# MC50_Pwr_MotDrv.net
KiCad netlist of a schematic drawn in Altium Designer
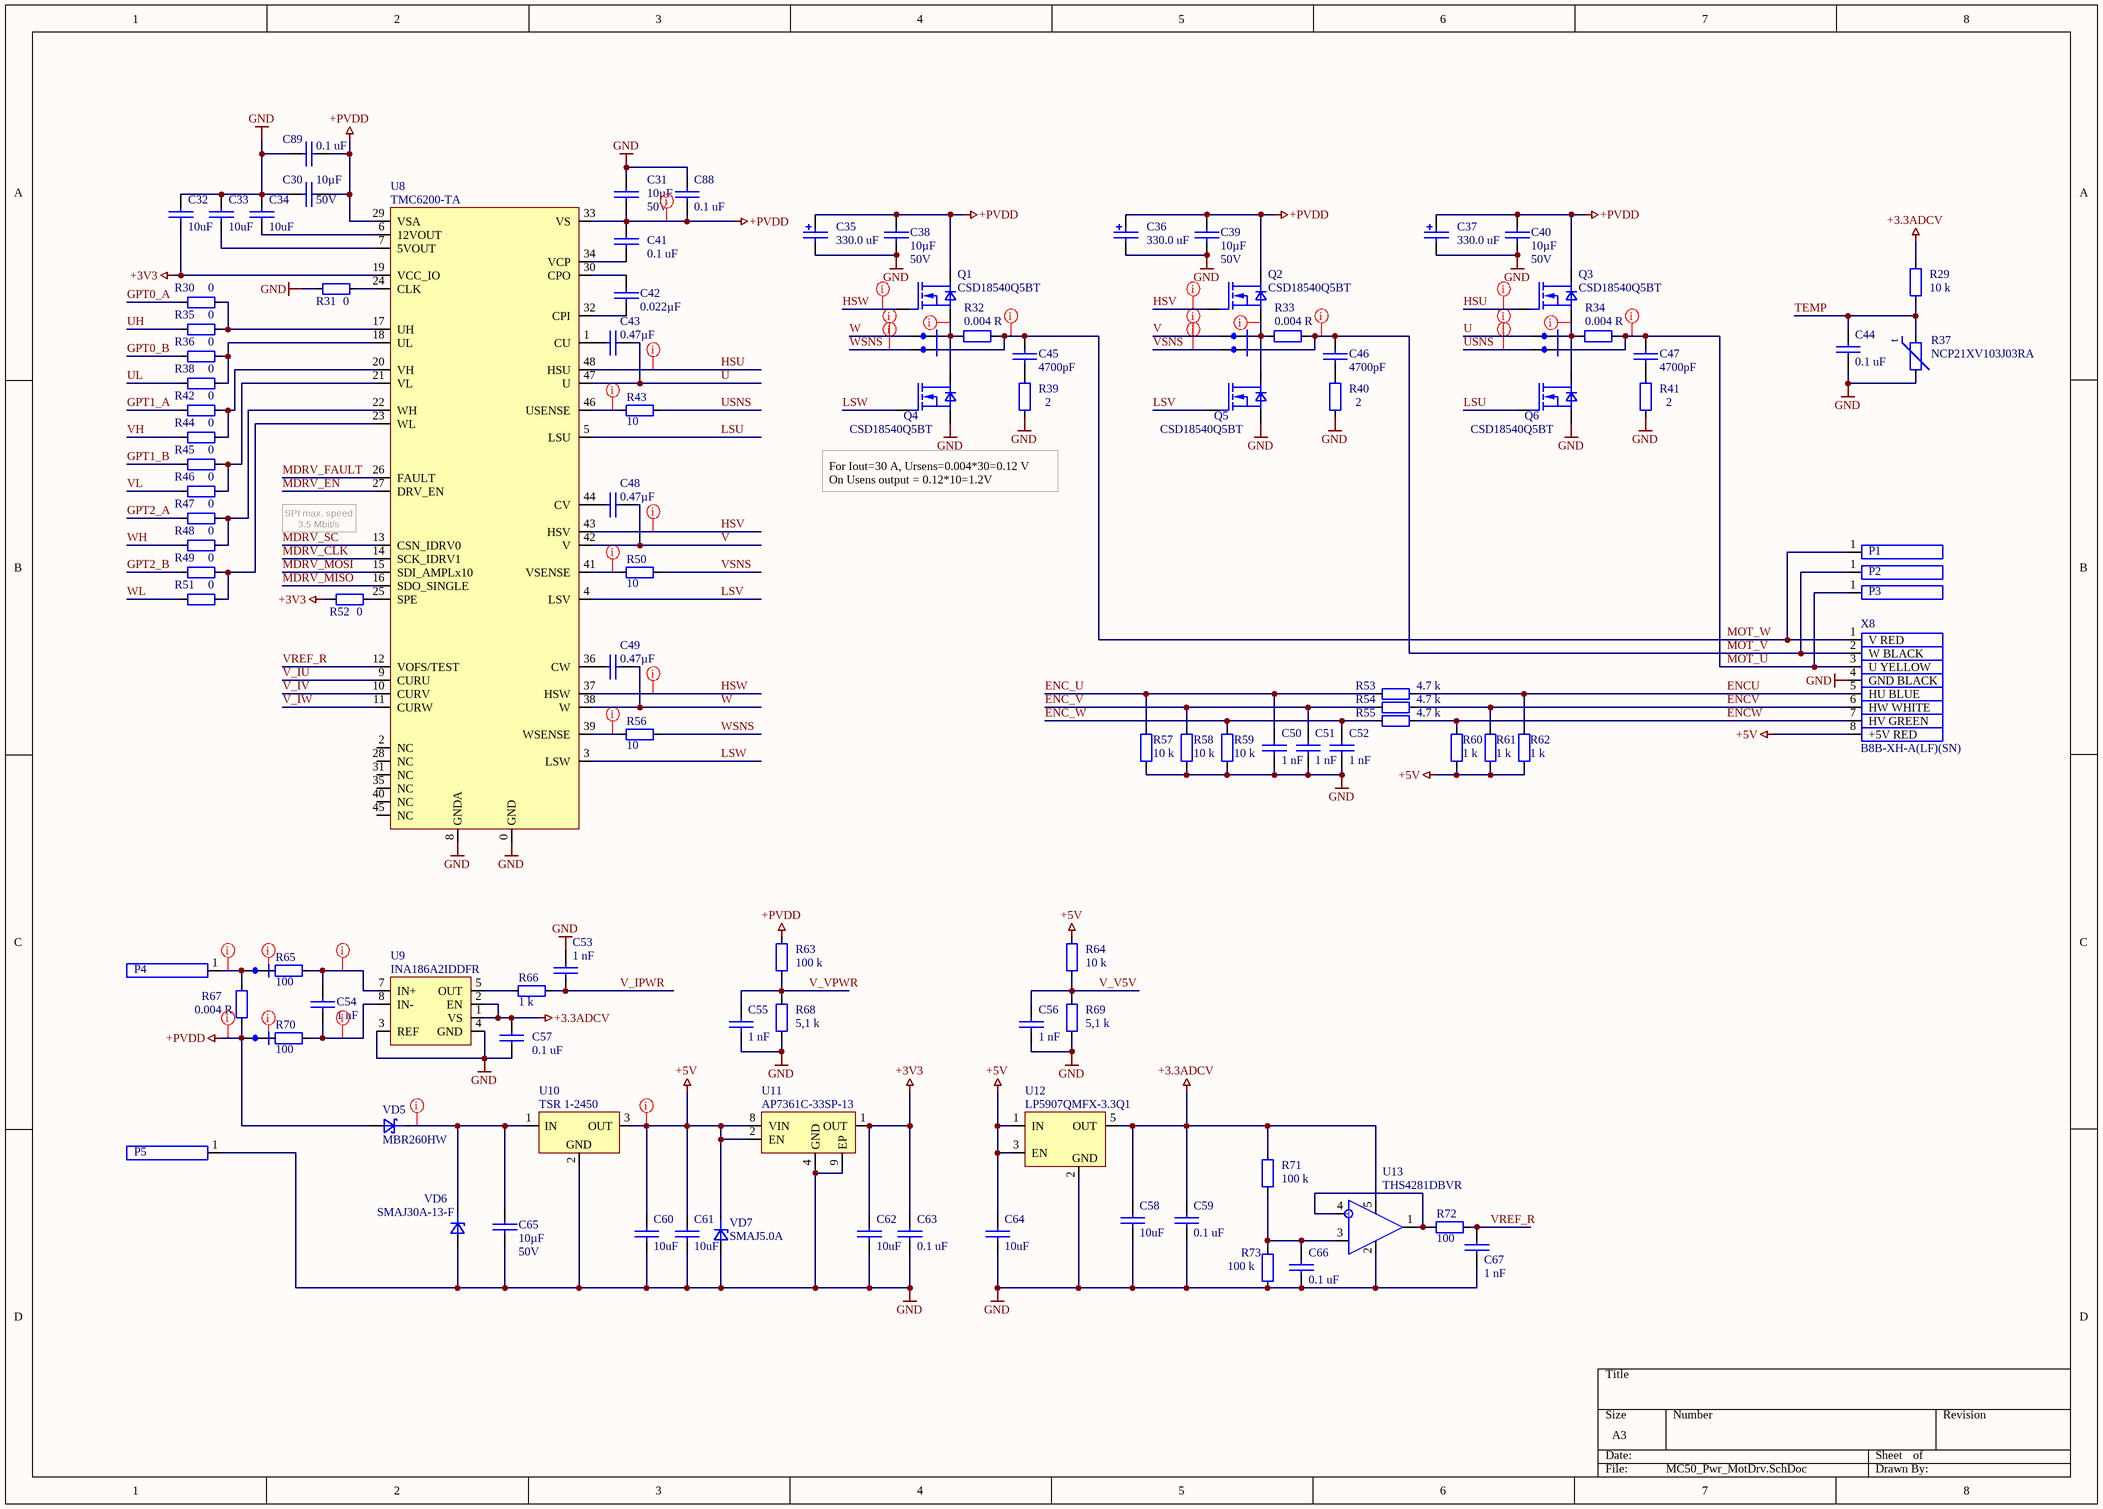
[diagram p0: MC50_Pwr_MotDrv.SchDoc]

(export (version "E")
  (design (tool "Eeschema 10.0.6"))
  (components
    (comp (ref "B1")
      (value "Current shunt net tie 0.4 mm")
      (footprint "Current shunt net tie 0.4 mm")
      (libsource (lib "ea_Net_tie") (part "Current shunt net tie 0.4 mm"))
    )
    (comp (ref "B2")
      (value "Current shunt net tie 0.4 mm")
      (footprint "Current shunt net tie 0.4 mm")
      (libsource (lib "ea_Net_tie") (part "Current shunt net tie 0.4 mm"))
    )
    (comp (ref "B3")
      (value "Current shunt net tie 0.4 mm")
      (footprint "Current shunt net tie 0.4 mm")
      (libsource (lib "ea_Net_tie") (part "Current shunt net tie 0.4 mm"))
    )
    (comp (ref "B4")
      (value "Current shunt net tie 0.4 mm")
      (footprint "Current shunt net tie 0.4 mm")
      (libsource (lib "ea_Net_tie") (part "Current shunt net tie 0.4 mm"))
    )
    (comp (ref "B5")
      (value "Current shunt net tie 0.4 mm")
      (footprint "Current shunt net tie 0.4 mm")
      (libsource (lib "ea_Net_tie") (part "Current shunt net tie 0.4 mm"))
    )
    (comp (ref "B6")
      (value "Current shunt net tie 0.4 mm")
      (footprint "Current shunt net tie 0.4 mm")
      (libsource (lib "ea_Net_tie") (part "Current shunt net tie 0.4 mm"))
    )
    (comp (ref "B7")
      (value "Current shunt net tie 0.4 mm")
      (footprint "Current shunt net tie 0.4 mm")
      (libsource (lib "ea_Net_tie") (part "Current shunt net tie 0.4 mm"))
    )
    (comp (ref "B8")
      (value "Current shunt net tie 0.4 mm")
      (footprint "Current shunt net tie 0.4 mm")
      (libsource (lib "ea_Net_tie") (part "Current shunt net tie 0.4 mm"))
    )
    (comp (ref "C30")
      (value "10µF")
      (footprint "1210 CAP")
      (description "10µF, ±10%, 50V, X7S, 1210 (3225 Metric), -55°C ~ 125°C, -, Automotive")
      (fields
        (field (name "VOLTAGE - RATED") "50V")
        (field (name "PART NUMBER") "GCM32EC71H106KA03K")
        (field (name "MANUFACTURER") "Murata Electronics North America")
      )
      (libsource (lib "ea_PassivComps") (part "Capacitor"))
    )
    (comp (ref "C31")
      (value "10µF")
      (footprint "1210 CAP")
      (description "10µF, ±10%, 50V, X7S, 1210 (3225 Metric), -55°C ~ 125°C, -, Automotive")
      (fields
        (field (name "VOLTAGE - RATED") "50V")
        (field (name "PART NUMBER") "GCM32EC71H106KA03K")
        (field (name "MANUFACTURER") "Murata Electronics North America")
      )
      (libsource (lib "ea_PassivComps") (part "Capacitor"))
    )
    (comp (ref "C32")
      (value "10uF")
      (footprint "1608[0603]")
      (description "10 µF ±10% 25V Ceramic Capacitor X5R 0603 (1608 Metric), -55°C ~ 85°C")
      (fields (field (name "MANUFACTURER") "Murata Electronics") (field (name "TOLERANCE") "±10%"))
      (libsource (lib "ea_Capacitors_0603") (part "GRM188R61E106KA73D"))
    )
    (comp (ref "C33")
      (value "10uF")
      (footprint "1608[0603]")
      (description "10 µF ±10% 25V Ceramic Capacitor X5R 0603 (1608 Metric), -55°C ~ 85°C")
      (fields (field (name "MANUFACTURER") "Murata Electronics") (field (name "TOLERANCE") "±10%"))
      (libsource (lib "ea_Capacitors_0603") (part "GRM188R61E106KA73D"))
    )
    (comp (ref "C34")
      (value "10uF")
      (footprint "1608[0603]")
      (description "10 µF ±10% 25V Ceramic Capacitor X5R 0603 (1608 Metric), -55°C ~ 85°C")
      (fields (field (name "MANUFACTURER") "Murata Electronics") (field (name "TOLERANCE") "±10%"))
      (libsource (lib "ea_Capacitors_0603") (part "GRM188R61E106KA73D"))
    )
    (comp (ref "C35")
      (value "330.0 uF")
      (footprint "UUD1V331MNL1GS")
      (description "330 uF, 50V, 120 mOhm @ 100kHz, 585 mA, 10x10, -50...+105 C")
      (fields (field (name "MANUFACTURER") "Panasonic Electronic Components") (field (name "VOLTAGE") "50 V"))
      (libsource (lib "ea_Capacitors") (part "EEE-FT1H331AP"))
    )
    (comp (ref "C36")
      (value "330.0 uF")
      (footprint "UUD1V331MNL1GS")
      (description "330 uF, 50V, 120 mOhm @ 100kHz, 585 mA, 10x10, -50...+105 C")
      (fields (field (name "MANUFACTURER") "Panasonic Electronic Components") (field (name "VOLTAGE") "50 V"))
      (libsource (lib "ea_Capacitors") (part "EEE-FT1H331AP"))
    )
    (comp (ref "C37")
      (value "330.0 uF")
      (footprint "UUD1V331MNL1GS")
      (description "330 uF, 50V, 120 mOhm @ 100kHz, 585 mA, 10x10, -50...+105 C")
      (fields (field (name "MANUFACTURER") "Panasonic Electronic Components") (field (name "VOLTAGE") "50 V"))
      (libsource (lib "ea_Capacitors") (part "EEE-FT1H331AP"))
    )
    (comp (ref "C38")
      (value "10µF")
      (footprint "1210 CAP")
      (description "10µF, ±10%, 50V, X7S, 1210 (3225 Metric), -55°C ~ 125°C, -, Automotive")
      (fields
        (field (name "VOLTAGE - RATED") "50V")
        (field (name "PART NUMBER") "GCM32EC71H106KA03K")
        (field (name "MANUFACTURER") "Murata Electronics North America")
      )
      (libsource (lib "ea_PassivComps") (part "Capacitor"))
    )
    (comp (ref "C39")
      (value "10µF")
      (footprint "1210 CAP")
      (description "10µF, ±10%, 50V, X7S, 1210 (3225 Metric), -55°C ~ 125°C, -, Automotive")
      (fields
        (field (name "VOLTAGE - RATED") "50V")
        (field (name "PART NUMBER") "GCM32EC71H106KA03K")
        (field (name "MANUFACTURER") "Murata Electronics North America")
      )
      (libsource (lib "ea_PassivComps") (part "Capacitor"))
    )
    (comp (ref "C40")
      (value "10µF")
      (footprint "1210 CAP")
      (description "10µF, ±10%, 50V, X7S, 1210 (3225 Metric), -55°C ~ 125°C, -, Automotive")
      (fields
        (field (name "VOLTAGE - RATED") "50V")
        (field (name "PART NUMBER") "GCM32EC71H106KA03K")
        (field (name "MANUFACTURER") "Murata Electronics North America")
      )
      (libsource (lib "ea_PassivComps") (part "Capacitor"))
    )
    (comp (ref "C41")
      (value "0.1 uF")
      (footprint "1608[0603]")
      (description "0.1 µF ±10% 50V Ceramic Capacitor X7R 0603 (1608 Metric),  \r\n-55°C ~ 125°C")
      (fields
        (field (name "TOLERANCE") "+-10%")
        (field (name "MANUFACTURER") "Walsin Technology Corporation")
      )
      (libsource (lib "ea_Capacitors_0603") (part "0603B104K500CT"))
    )
    (comp (ref "C42")
      (value "0.022µF")
      (footprint "0603 CAP")
      (description "0.022µF, ±10%, 50V, X7R, 0603 (1608 Metric), -55°C ~ 125°C, -, General Purpose")
      (fields (field (name "PART NUMBER") "06035C223KAT4A") (field (name "MANUFACTURER") "AVX Corporation"))
      (libsource (lib "ea_PassivComps") (part "Capacitor"))
    )
    (comp (ref "C43")
      (value "0.47µF")
      (footprint "0603 CAP")
      (description "0.47µF, -20%, +80%, 50V, Y5V (F), 0603 (1608 Metric), -30°C ~ 85°C, -, General Purpose")
      (fields
        (field (name "PART NUMBER") "CL10F474ZB8NNNC")
        (field (name "MANUFACTURER") "Samsung Electro-Mechanics")
      )
      (libsource (lib "ea_PassivComps") (part "Capacitor"))
    )
    (comp (ref "C44")
      (value "0.1 uF")
      (footprint "1608[0603]")
      (description "0.1 µF ±10% 50V Ceramic Capacitor X7R 0603 (1608 Metric),  \r\n-55°C ~ 125°C")
      (fields
        (field (name "TOLERANCE") "+-10%")
        (field (name "MANUFACTURER") "Walsin Technology Corporation")
      )
      (libsource (lib "ea_Capacitors_0603") (part "0603B104K500CT"))
    )
    (comp (ref "C45")
      (value "4700pF")
      (footprint "0805 CAP")
      (description "4700pF, ±10%, 100V, X7R, 0805 (2012 Metric), -55°C ~ 125°C, -, General Purpose")
      (fields
        (field (name "PART NUMBER") "CL21B472KCANNNC")
        (field (name "MANUFACTURER") "Samsung Electro-Mechanics")
      )
      (libsource (lib "ea_PassivComps") (part "Capacitor"))
    )
    (comp (ref "C46")
      (value "4700pF")
      (footprint "0805 CAP")
      (description "4700pF, ±10%, 100V, X7R, 0805 (2012 Metric), -55°C ~ 125°C, -, General Purpose")
      (fields
        (field (name "PART NUMBER") "CL21B472KCANNNC")
        (field (name "MANUFACTURER") "Samsung Electro-Mechanics")
      )
      (libsource (lib "ea_PassivComps") (part "Capacitor"))
    )
    (comp (ref "C47")
      (value "4700pF")
      (footprint "0805 CAP")
      (description "4700pF, ±10%, 100V, X7R, 0805 (2012 Metric), -55°C ~ 125°C, -, General Purpose")
      (fields
        (field (name "PART NUMBER") "CL21B472KCANNNC")
        (field (name "MANUFACTURER") "Samsung Electro-Mechanics")
      )
      (libsource (lib "ea_PassivComps") (part "Capacitor"))
    )
    (comp (ref "C48")
      (value "0.47µF")
      (footprint "0603 CAP")
      (description "0.47µF, -20%, +80%, 50V, Y5V (F), 0603 (1608 Metric), -30°C ~ 85°C, -, General Purpose")
      (fields
        (field (name "PART NUMBER") "CL10F474ZB8NNNC")
        (field (name "MANUFACTURER") "Samsung Electro-Mechanics")
      )
      (libsource (lib "ea_PassivComps") (part "Capacitor"))
    )
    (comp (ref "C49")
      (value "0.47µF")
      (footprint "0603 CAP")
      (description "0.47µF, -20%, +80%, 50V, Y5V (F), 0603 (1608 Metric), -30°C ~ 85°C, -, General Purpose")
      (fields
        (field (name "PART NUMBER") "CL10F474ZB8NNNC")
        (field (name "MANUFACTURER") "Samsung Electro-Mechanics")
      )
      (libsource (lib "ea_PassivComps") (part "Capacitor"))
    )
    (comp (ref "C50")
      (value "1 nF")
      (footprint "0603 CAP")
      (description "1000pF, ±5%, 50V, X7R, 0603 (1608 Metric), -55°C ~ 125°C, -, General Purpose")
      (fields (field (name "PART NUMBER") "CC0603JRX7R9BB102") (field (name "MANUFACTURER") "Yageo"))
      (libsource (lib "ea_PassivComps") (part "Capacitor"))
    )
    (comp (ref "C51")
      (value "1 nF")
      (footprint "0603 CAP")
      (description "1000pF, ±5%, 50V, X7R, 0603 (1608 Metric), -55°C ~ 125°C, -, General Purpose")
      (fields (field (name "PART NUMBER") "CC0603JRX7R9BB102") (field (name "MANUFACTURER") "Yageo"))
      (libsource (lib "ea_PassivComps") (part "Capacitor"))
    )
    (comp (ref "C52")
      (value "1 nF")
      (footprint "0603 CAP")
      (description "1000pF, ±5%, 50V, X7R, 0603 (1608 Metric), -55°C ~ 125°C, -, General Purpose")
      (fields (field (name "PART NUMBER") "CC0603JRX7R9BB102") (field (name "MANUFACTURER") "Yageo"))
      (libsource (lib "ea_PassivComps") (part "Capacitor"))
    )
    (comp (ref "C53")
      (value "1 nF")
      (footprint "0603 CAP")
      (description "1000pF, ±5%, 50V, X7R, 0603 (1608 Metric), -55°C ~ 125°C, -, General Purpose")
      (fields (field (name "PART NUMBER") "CC0603JRX7R9BB102") (field (name "MANUFACTURER") "Yageo"))
      (libsource (lib "ea_PassivComps") (part "Capacitor"))
    )
    (comp (ref "C54")
      (value "1 nF")
      (footprint "0603 CAP")
      (description "1000pF, ±5%, 50V, X7R, 0603 (1608 Metric), -55°C ~ 125°C, -, General Purpose")
      (fields (field (name "PART NUMBER") "CC0603JRX7R9BB102") (field (name "MANUFACTURER") "Yageo"))
      (libsource (lib "ea_PassivComps") (part "Capacitor"))
    )
    (comp (ref "C55")
      (value "1 nF")
      (footprint "0603 CAP")
      (description "1000pF, ±5%, 50V, X7R, 0603 (1608 Metric), -55°C ~ 125°C, -, General Purpose")
      (fields (field (name "PART NUMBER") "CC0603JRX7R9BB102") (field (name "MANUFACTURER") "Yageo"))
      (libsource (lib "ea_PassivComps") (part "Capacitor"))
    )
    (comp (ref "C56")
      (value "1 nF")
      (footprint "0603 CAP")
      (description "1000pF, ±5%, 50V, X7R, 0603 (1608 Metric), -55°C ~ 125°C, -, General Purpose")
      (fields (field (name "PART NUMBER") "CC0603JRX7R9BB102") (field (name "MANUFACTURER") "Yageo"))
      (libsource (lib "ea_PassivComps") (part "Capacitor"))
    )
    (comp (ref "C57")
      (value "0.1 uF")
      (footprint "1608[0603]")
      (description "0.1 µF ±10% 50V Ceramic Capacitor X7R 0603 (1608 Metric),  \r\n-55°C ~ 125°C")
      (fields
        (field (name "TOLERANCE") "+-10%")
        (field (name "MANUFACTURER") "Walsin Technology Corporation")
      )
      (libsource (lib "ea_Capacitors_0603") (part "0603B104K500CT"))
    )
    (comp (ref "C58")
      (value "10uF")
      (footprint "1608[0603]")
      (description "10 µF ±10% 25V Ceramic Capacitor X5R 0603 (1608 Metric), -55°C ~ 85°C")
      (fields (field (name "MANUFACTURER") "Murata Electronics") (field (name "TOLERANCE") "±10%"))
      (libsource (lib "ea_Capacitors_0603") (part "GRM188R61E106KA73D"))
    )
    (comp (ref "C59")
      (value "0.1 uF")
      (footprint "1608[0603]")
      (description "0.1 µF ±10% 50V Ceramic Capacitor X7R 0603 (1608 Metric),  \r\n-55°C ~ 125°C")
      (fields
        (field (name "TOLERANCE") "+-10%")
        (field (name "MANUFACTURER") "Walsin Technology Corporation")
      )
      (libsource (lib "ea_Capacitors_0603") (part "0603B104K500CT"))
    )
    (comp (ref "C60")
      (value "10uF")
      (footprint "1608[0603]")
      (description "10 µF ±10% 25V Ceramic Capacitor X5R 0603 (1608 Metric), -55°C ~ 85°C")
      (fields (field (name "MANUFACTURER") "Murata Electronics") (field (name "TOLERANCE") "±10%"))
      (libsource (lib "ea_Capacitors_0603") (part "GRM188R61E106KA73D"))
    )
    (comp (ref "C61")
      (value "10uF")
      (footprint "1608[0603]")
      (description "10 µF ±10% 25V Ceramic Capacitor X5R 0603 (1608 Metric), -55°C ~ 85°C")
      (fields (field (name "MANUFACTURER") "Murata Electronics") (field (name "TOLERANCE") "±10%"))
      (libsource (lib "ea_Capacitors_0603") (part "GRM188R61E106KA73D"))
    )
    (comp (ref "C62")
      (value "10uF")
      (footprint "1608[0603]")
      (description "10 µF ±10% 25V Ceramic Capacitor X5R 0603 (1608 Metric), -55°C ~ 85°C")
      (fields (field (name "MANUFACTURER") "Murata Electronics") (field (name "TOLERANCE") "±10%"))
      (libsource (lib "ea_Capacitors_0603") (part "GRM188R61E106KA73D"))
    )
    (comp (ref "C63")
      (value "0.1 uF")
      (footprint "1608[0603]")
      (description "0.1 µF ±10% 50V Ceramic Capacitor X7R 0603 (1608 Metric),  \r\n-55°C ~ 125°C")
      (fields
        (field (name "TOLERANCE") "+-10%")
        (field (name "MANUFACTURER") "Walsin Technology Corporation")
      )
      (libsource (lib "ea_Capacitors_0603") (part "0603B104K500CT"))
    )
    (comp (ref "C64")
      (value "10uF")
      (footprint "1608[0603]")
      (description "10 µF ±10% 25V Ceramic Capacitor X5R 0603 (1608 Metric), -55°C ~ 85°C")
      (fields (field (name "MANUFACTURER") "Murata Electronics") (field (name "TOLERANCE") "±10%"))
      (libsource (lib "ea_Capacitors_0603") (part "GRM188R61E106KA73D"))
    )
    (comp (ref "C65")
      (value "10µF")
      (footprint "1210 CAP")
      (description "10µF, ±10%, 50V, X7S, 1210 (3225 Metric), -55°C ~ 125°C, -, Automotive")
      (fields
        (field (name "VOLTAGE - RATED") "50V")
        (field (name "PART NUMBER") "GCM32EC71H106KA03K")
        (field (name "MANUFACTURER") "Murata Electronics North America")
      )
      (libsource (lib "ea_PassivComps") (part "Capacitor"))
    )
    (comp (ref "C66")
      (value "0.1 uF")
      (footprint "1608[0603]")
      (description "0.1 µF ±10% 50V Ceramic Capacitor X7R 0603 (1608 Metric),  \r\n-55°C ~ 125°C")
      (fields
        (field (name "TOLERANCE") "+-10%")
        (field (name "MANUFACTURER") "Walsin Technology Corporation")
      )
      (libsource (lib "ea_Capacitors_0603") (part "0603B104K500CT"))
    )
    (comp (ref "C67")
      (value "1 nF")
      (footprint "0603 CAP")
      (description "1000pF, ±5%, 50V, X7R, 0603 (1608 Metric), -55°C ~ 125°C, -, General Purpose")
      (fields (field (name "PART NUMBER") "CC0603JRX7R9BB102") (field (name "MANUFACTURER") "Yageo"))
      (libsource (lib "ea_PassivComps") (part "Capacitor"))
    )
    (comp (ref "C88")
      (value "0.1 uF")
      (footprint "1608[0603]")
      (description "0.1 µF ±10% 50V Ceramic Capacitor X7R 0603 (1608 Metric),  \r\n-55°C ~ 125°C")
      (fields
        (field (name "TOLERANCE") "+-10%")
        (field (name "MANUFACTURER") "Walsin Technology Corporation")
      )
      (libsource (lib "ea_Capacitors_0603") (part "0603B104K500CT"))
    )
    (comp (ref "C89")
      (value "0.1 uF")
      (footprint "1608[0603]")
      (description "0.1 µF ±10% 50V Ceramic Capacitor X7R 0603 (1608 Metric),  \r\n-55°C ~ 125°C")
      (fields
        (field (name "TOLERANCE") "+-10%")
        (field (name "MANUFACTURER") "Walsin Technology Corporation")
      )
      (libsource (lib "ea_Capacitors_0603") (part "0603B104K500CT"))
    )
    (comp (ref "P1")
      (value "Keystone 1212")
      (footprint "Keystone 1212")
      (description "(4.75mm) Quick Connect Male Solder Connector Non-Insulated")
      (fields (field (name "MANUFACTURER") "Keystone Electronics") (field (name "PARTNUM") "36-1212-ND"))
      (libsource (lib "ea_Connectors_Power") (part "Keystone_1212"))
    )
    (comp (ref "P2")
      (value "Keystone 1212")
      (footprint "Keystone 1212")
      (description "(4.75mm) Quick Connect Male Solder Connector Non-Insulated")
      (fields (field (name "MANUFACTURER") "Keystone Electronics") (field (name "PARTNUM") "36-1212-ND"))
      (libsource (lib "ea_Connectors_Power") (part "Keystone_1212"))
    )
    (comp (ref "P3")
      (value "Keystone 1212")
      (footprint "Keystone 1212")
      (description "(4.75mm) Quick Connect Male Solder Connector Non-Insulated")
      (fields (field (name "MANUFACTURER") "Keystone Electronics") (field (name "PARTNUM") "36-1212-ND"))
      (libsource (lib "ea_Connectors_Power") (part "Keystone_1212"))
    )
    (comp (ref "P4")
      (value "Keystone 1212")
      (footprint "Keystone 1212")
      (description "(4.75mm) Quick Connect Male Solder Connector Non-Insulated")
      (fields (field (name "MANUFACTURER") "Keystone Electronics") (field (name "PARTNUM") "36-1212-ND"))
      (libsource (lib "ea_Connectors_Power") (part "Keystone_1212"))
    )
    (comp (ref "P5")
      (value "Keystone 1212")
      (footprint "Keystone 1212")
      (description "(4.75mm) Quick Connect Male Solder Connector Non-Insulated")
      (fields (field (name "MANUFACTURER") "Keystone Electronics") (field (name "PARTNUM") "36-1212-ND"))
      (libsource (lib "ea_Connectors_Power") (part "Keystone_1212"))
    )
    (comp (ref "Q1")
      (value "CSD18540Q5BT")
      (footprint "SO8FL Universal Footprint")
      (description "MOSFET N-CH, 100 A, 60V, Vgs=±20V, 1.8 mOhm, 41nC @ 10V, 5-DFN (5x6), -55°C ~ 150°C")
      (fields (field (name "MANUFACTURER") "Texas Instruments") (field (name "PARTNUM") "296-37963-1-ND"))
      (libsource (lib "ea_MOSFET_&_drivers") (part "CSD18540Q5BT"))
    )
    (comp (ref "Q2")
      (value "CSD18540Q5BT")
      (footprint "SO8FL Universal Footprint")
      (description "MOSFET N-CH, 100 A, 60V, Vgs=±20V, 1.8 mOhm, 41nC @ 10V, 5-DFN (5x6), -55°C ~ 150°C")
      (fields (field (name "MANUFACTURER") "Texas Instruments") (field (name "PARTNUM") "296-37963-1-ND"))
      (libsource (lib "ea_MOSFET_&_drivers") (part "CSD18540Q5BT"))
    )
    (comp (ref "Q3")
      (value "CSD18540Q5BT")
      (footprint "SO8FL Universal Footprint")
      (description "MOSFET N-CH, 100 A, 60V, Vgs=±20V, 1.8 mOhm, 41nC @ 10V, 5-DFN (5x6), -55°C ~ 150°C")
      (fields (field (name "MANUFACTURER") "Texas Instruments") (field (name "PARTNUM") "296-37963-1-ND"))
      (libsource (lib "ea_MOSFET_&_drivers") (part "CSD18540Q5BT"))
    )
    (comp (ref "Q4")
      (value "CSD18540Q5BT")
      (footprint "SO8FL Universal Footprint")
      (description "MOSFET N-CH, 100 A, 60V, Vgs=±20V, 1.8 mOhm, 41nC @ 10V, 5-DFN (5x6), -55°C ~ 150°C")
      (fields (field (name "MANUFACTURER") "Texas Instruments") (field (name "PARTNUM") "296-37963-1-ND"))
      (libsource (lib "ea_MOSFET_&_drivers") (part "CSD18540Q5BT"))
    )
    (comp (ref "Q5")
      (value "CSD18540Q5BT")
      (footprint "SO8FL Universal Footprint")
      (description "MOSFET N-CH, 100 A, 60V, Vgs=±20V, 1.8 mOhm, 41nC @ 10V, 5-DFN (5x6), -55°C ~ 150°C")
      (fields (field (name "MANUFACTURER") "Texas Instruments") (field (name "PARTNUM") "296-37963-1-ND"))
      (libsource (lib "ea_MOSFET_&_drivers") (part "CSD18540Q5BT"))
    )
    (comp (ref "Q6")
      (value "CSD18540Q5BT")
      (footprint "SO8FL Universal Footprint")
      (description "MOSFET N-CH, 100 A, 60V, Vgs=±20V, 1.8 mOhm, 41nC @ 10V, 5-DFN (5x6), -55°C ~ 150°C")
      (fields (field (name "MANUFACTURER") "Texas Instruments") (field (name "PARTNUM") "296-37963-1-ND"))
      (libsource (lib "ea_MOSFET_&_drivers") (part "CSD18540Q5BT"))
    )
    (comp (ref "R29")
      (value "10 k")
      (footprint "0603")
      (fields
        (field (name "MANUFACTURER") "Stackpole Electronics Inc")
        (field (name "TOLERANCE") "±0.1%")
        (field (name "VOLTAGE") "75V")
      )
      (libsource (lib "ea_PassivComps") (part "Resistor"))
    )
    (comp (ref "R30")
      (value "0")
      (footprint "0603")
      (description "0 Ohms, 0.1W, 1/10W, Thick Film, 0603 (1608 Metric), -55°C ~ 155°C, Automotive AEC-Q200")
      (fields
        (field (name "MANUFACTURER") "Stackpole Electronics Inc.")
        (field (name "PARTNUM") "RMCF0603ZT0R00CT-ND")
      )
      (libsource (lib "") (part "Resistor_1"))
    )
    (comp (ref "R31")
      (value "0")
      (footprint "0603")
      (description "0 Ohms, 0.1W, 1/10W, Thick Film, 0603 (1608 Metric), -55°C ~ 155°C, Automotive AEC-Q200")
      (fields
        (field (name "MANUFACTURER") "Stackpole Electronics Inc.")
        (field (name "PARTNUM") "RMCF0603ZT0R00CT-ND")
      )
      (libsource (lib "") (part "Resistor_1"))
    )
    (comp (ref "R32")
      (value "0.004 R")
      (footprint "CSNL2512 CURR SENS")
      (description "Curr.sens.res. 0.004 OHM, 2W, 1% , ±50ppm/°C, 2512 (6432 Metric)")
      (fields (field (name "MANUFACTURER") "Stackpole Electronics Inc.") (field (name "TOLERANCE") "±1%"))
      (libsource (lib "ea_Resistors") (part "CSNL2512FT4L00"))
    )
    (comp (ref "R33")
      (value "0.004 R")
      (footprint "CSNL2512 CURR SENS")
      (description "Curr.sens.res. 0.004 OHM, 2W, 1% , ±50ppm/°C, 2512 (6432 Metric)")
      (fields (field (name "MANUFACTURER") "Stackpole Electronics Inc.") (field (name "TOLERANCE") "±1%"))
      (libsource (lib "ea_Resistors") (part "CSNL2512FT4L00"))
    )
    (comp (ref "R34")
      (value "0.004 R")
      (footprint "CSNL2512 CURR SENS")
      (description "Curr.sens.res. 0.004 OHM, 2W, 1% , ±50ppm/°C, 2512 (6432 Metric)")
      (fields (field (name "MANUFACTURER") "Stackpole Electronics Inc.") (field (name "TOLERANCE") "±1%"))
      (libsource (lib "ea_Resistors") (part "CSNL2512FT4L00"))
    )
    (comp (ref "R35")
      (value "0")
      (footprint "0603")
      (description "0 Ohms, 0.1W, 1/10W, Thick Film, 0603 (1608 Metric), -55°C ~ 155°C, Automotive AEC-Q200")
      (fields
        (field (name "MANUFACTURER") "Stackpole Electronics Inc.")
        (field (name "PARTNUM") "RMCF0603ZT0R00CT-ND")
      )
      (libsource (lib "") (part "Resistor_1"))
    )
    (comp (ref "R36")
      (value "0")
      (footprint "0603")
      (description "0 Ohms, 0.1W, 1/10W, Thick Film, 0603 (1608 Metric), -55°C ~ 155°C, Automotive AEC-Q200")
      (fields
        (field (name "MANUFACTURER") "Stackpole Electronics Inc.")
        (field (name "PARTNUM") "RMCF0603ZT0R00CT-ND")
      )
      (libsource (lib "") (part "Resistor_1"))
    )
    (comp (ref "R37")
      (value "NCP21XV103J03RA")
      (footprint "0805")
      (description "Thermistor 10k, 0805, NTC")
      (fields (field (name "MANUFACTURER") "Murata") (field (name "PARTNUM") "490-2456-1-ND"))
      (libsource (lib "ea_IC_sensors") (part "NCP21XV103J03RA"))
    )
    (comp (ref "R38")
      (value "0")
      (footprint "0603")
      (description "0 Ohms, 0.1W, 1/10W, Thick Film, 0603 (1608 Metric), -55°C ~ 155°C, Automotive AEC-Q200")
      (fields
        (field (name "MANUFACTURER") "Stackpole Electronics Inc.")
        (field (name "PARTNUM") "RMCF0603ZT0R00CT-ND")
      )
      (libsource (lib "") (part "Resistor_1"))
    )
    (comp (ref "R39")
      (value "2")
      (footprint "0805")
      (description "2 Ohms, ±1%, 0.125W, 1/8W, Thick Film, ±100ppm/°C, 0805 (2012 Metric), -55°C ~ 155°C, -")
      (fields (field (name "MANUFACTURER") "Vishay Dale") (field (name "TOLERANCE") "±1%"))
      (libsource (lib "ea_PassivComps") (part "Resistor"))
    )
    (comp (ref "R40")
      (value "2")
      (footprint "0805")
      (description "2 Ohms, ±1%, 0.125W, 1/8W, Thick Film, ±100ppm/°C, 0805 (2012 Metric), -55°C ~ 155°C, -")
      (fields (field (name "MANUFACTURER") "Vishay Dale") (field (name "TOLERANCE") "±1%"))
      (libsource (lib "ea_PassivComps") (part "Resistor"))
    )
    (comp (ref "R41")
      (value "2")
      (footprint "0805")
      (description "2 Ohms, ±1%, 0.125W, 1/8W, Thick Film, ±100ppm/°C, 0805 (2012 Metric), -55°C ~ 155°C, -")
      (fields (field (name "MANUFACTURER") "Vishay Dale") (field (name "TOLERANCE") "±1%"))
      (libsource (lib "ea_PassivComps") (part "Resistor"))
    )
    (comp (ref "R42")
      (value "0")
      (footprint "0603")
      (description "0 Ohms, 0.1W, 1/10W, Thick Film, 0603 (1608 Metric), -55°C ~ 155°C, Automotive AEC-Q200")
      (fields
        (field (name "MANUFACTURER") "Stackpole Electronics Inc.")
        (field (name "PARTNUM") "RMCF0603ZT0R00CT-ND")
      )
      (libsource (lib "") (part "Resistor_1"))
    )
    (comp (ref "R43")
      (value "10")
      (footprint "0603")
      (fields
        (field (name "MANUFACTURER") "Panasonic Electronic Components")
        (field (name "TOLERANCE") "±1%")
        (field (name "VOLTAGE") "75V")
      )
      (libsource (lib "") (part "Resistor_1"))
    )
    (comp (ref "R44")
      (value "0")
      (footprint "0603")
      (description "0 Ohms, 0.1W, 1/10W, Thick Film, 0603 (1608 Metric), -55°C ~ 155°C, Automotive AEC-Q200")
      (fields
        (field (name "MANUFACTURER") "Stackpole Electronics Inc.")
        (field (name "PARTNUM") "RMCF0603ZT0R00CT-ND")
      )
      (libsource (lib "") (part "Resistor_1"))
    )
    (comp (ref "R45")
      (value "0")
      (footprint "0603")
      (description "0 Ohms, 0.1W, 1/10W, Thick Film, 0603 (1608 Metric), -55°C ~ 155°C, Automotive AEC-Q200")
      (fields
        (field (name "MANUFACTURER") "Stackpole Electronics Inc.")
        (field (name "PARTNUM") "RMCF0603ZT0R00CT-ND")
      )
      (libsource (lib "") (part "Resistor_1"))
    )
    (comp (ref "R46")
      (value "0")
      (footprint "0603")
      (description "0 Ohms, 0.1W, 1/10W, Thick Film, 0603 (1608 Metric), -55°C ~ 155°C, Automotive AEC-Q200")
      (fields
        (field (name "MANUFACTURER") "Stackpole Electronics Inc.")
        (field (name "PARTNUM") "RMCF0603ZT0R00CT-ND")
      )
      (libsource (lib "") (part "Resistor_1"))
    )
    (comp (ref "R47")
      (value "0")
      (footprint "0603")
      (description "0 Ohms, 0.1W, 1/10W, Thick Film, 0603 (1608 Metric), -55°C ~ 155°C, Automotive AEC-Q200")
      (fields
        (field (name "MANUFACTURER") "Stackpole Electronics Inc.")
        (field (name "PARTNUM") "RMCF0603ZT0R00CT-ND")
      )
      (libsource (lib "") (part "Resistor_1"))
    )
    (comp (ref "R48")
      (value "0")
      (footprint "0603")
      (description "0 Ohms, 0.1W, 1/10W, Thick Film, 0603 (1608 Metric), -55°C ~ 155°C, Automotive AEC-Q200")
      (fields
        (field (name "MANUFACTURER") "Stackpole Electronics Inc.")
        (field (name "PARTNUM") "RMCF0603ZT0R00CT-ND")
      )
      (libsource (lib "") (part "Resistor_1"))
    )
    (comp (ref "R49")
      (value "0")
      (footprint "0603")
      (description "0 Ohms, 0.1W, 1/10W, Thick Film, 0603 (1608 Metric), -55°C ~ 155°C, Automotive AEC-Q200")
      (fields
        (field (name "MANUFACTURER") "Stackpole Electronics Inc.")
        (field (name "PARTNUM") "RMCF0603ZT0R00CT-ND")
      )
      (libsource (lib "") (part "Resistor_1"))
    )
    (comp (ref "R50")
      (value "10")
      (footprint "0603")
      (fields
        (field (name "MANUFACTURER") "Panasonic Electronic Components")
        (field (name "TOLERANCE") "±1%")
        (field (name "VOLTAGE") "75V")
      )
      (libsource (lib "") (part "Resistor_1"))
    )
    (comp (ref "R51")
      (value "0")
      (footprint "0603")
      (description "0 Ohms, 0.1W, 1/10W, Thick Film, 0603 (1608 Metric), -55°C ~ 155°C, Automotive AEC-Q200")
      (fields
        (field (name "MANUFACTURER") "Stackpole Electronics Inc.")
        (field (name "PARTNUM") "RMCF0603ZT0R00CT-ND")
      )
      (libsource (lib "") (part "Resistor_1"))
    )
    (comp (ref "R52")
      (value "0")
      (footprint "0603")
      (description "0 Ohms, 0.1W, 1/10W, Thick Film, 0603 (1608 Metric), -55°C ~ 155°C, Automotive AEC-Q200")
      (fields
        (field (name "MANUFACTURER") "Stackpole Electronics Inc.")
        (field (name "PARTNUM") "RMCF0603ZT0R00CT-ND")
      )
      (libsource (lib "") (part "Resistor_1"))
    )
    (comp (ref "R53")
      (value "4.7 k")
      (footprint "0603")
      (fields
        (field (name "MANUFACTURER") "Stackpole Electronics Inc.")
        (field (name "TOLERANCE") "±1%")
        (field (name "VOLTAGE") "75V")
      )
      (libsource (lib "") (part "Resistor_2"))
    )
    (comp (ref "R54")
      (value "4.7 k")
      (footprint "0603")
      (fields
        (field (name "MANUFACTURER") "Stackpole Electronics Inc.")
        (field (name "TOLERANCE") "±1%")
        (field (name "VOLTAGE") "75V")
      )
      (libsource (lib "") (part "Resistor_2"))
    )
    (comp (ref "R55")
      (value "4.7 k")
      (footprint "0603")
      (fields
        (field (name "MANUFACTURER") "Stackpole Electronics Inc.")
        (field (name "TOLERANCE") "±1%")
        (field (name "VOLTAGE") "75V")
      )
      (libsource (lib "") (part "Resistor_2"))
    )
    (comp (ref "R56")
      (value "10")
      (footprint "0603")
      (fields
        (field (name "MANUFACTURER") "Panasonic Electronic Components")
        (field (name "TOLERANCE") "±1%")
        (field (name "VOLTAGE") "75V")
      )
      (libsource (lib "") (part "Resistor_1"))
    )
    (comp (ref "R57")
      (value "10 k")
      (footprint "0603")
      (fields
        (field (name "MANUFACTURER") "Bourns Inc.")
        (field (name "TOLERANCE") "±1%")
        (field (name "VOLTAGE") "75V")
      )
      (libsource (lib "ea_PassivComps") (part "Resistor"))
    )
    (comp (ref "R58")
      (value "10 k")
      (footprint "0603")
      (fields
        (field (name "MANUFACTURER") "Bourns Inc.")
        (field (name "TOLERANCE") "±1%")
        (field (name "VOLTAGE") "75V")
      )
      (libsource (lib "ea_PassivComps") (part "Resistor"))
    )
    (comp (ref "R59")
      (value "10 k")
      (footprint "0603")
      (fields
        (field (name "MANUFACTURER") "Bourns Inc.")
        (field (name "TOLERANCE") "±1%")
        (field (name "VOLTAGE") "75V")
      )
      (libsource (lib "ea_PassivComps") (part "Resistor"))
    )
    (comp (ref "R60")
      (value "1 k")
      (footprint "0603")
      (fields
        (field (name "MANUFACTURER") "Stackpole Electronics Inc.")
        (field (name "TOLERANCE") "±1%")
        (field (name "VOLTAGE") "75V")
      )
      (libsource (lib "ea_PassivComps") (part "Resistor"))
    )
    (comp (ref "R61")
      (value "1 k")
      (footprint "0603")
      (fields
        (field (name "MANUFACTURER") "Stackpole Electronics Inc.")
        (field (name "TOLERANCE") "±1%")
        (field (name "VOLTAGE") "75V")
      )
      (libsource (lib "ea_PassivComps") (part "Resistor"))
    )
    (comp (ref "R62")
      (value "1 k")
      (footprint "0603")
      (fields
        (field (name "MANUFACTURER") "Stackpole Electronics Inc.")
        (field (name "TOLERANCE") "±1%")
        (field (name "VOLTAGE") "75V")
      )
      (libsource (lib "ea_PassivComps") (part "Resistor"))
    )
    (comp (ref "R63")
      (value "100 k")
      (footprint "0603")
      (fields
        (field (name "MANUFACTURER") "Susumu")
        (field (name "TOLERANCE") "±0.1%")
        (field (name "VOLTAGE") "75V")
      )
      (libsource (lib "ea_PassivComps") (part "Resistor"))
    )
    (comp (ref "R64")
      (value "10 k")
      (footprint "0603")
      (fields
        (field (name "MANUFACTURER") "Stackpole Electronics Inc")
        (field (name "TOLERANCE") "±0.1%")
        (field (name "VOLTAGE") "75V")
      )
      (libsource (lib "ea_PassivComps") (part "Resistor"))
    )
    (comp (ref "R65")
      (value "100")
      (footprint "0603")
      (fields
        (field (name "MANUFACTURER") "Stackpole Electronics Inc.")
        (field (name "TOLERANCE") "±1%")
        (field (name "VOLTAGE") "75V")
      )
      (libsource (lib "ea_PassivComps") (part "Resistor"))
    )
    (comp (ref "R66")
      (value "1 k")
      (footprint "0603")
      (fields
        (field (name "MANUFACTURER") "Stackpole Electronics Inc.")
        (field (name "TOLERANCE") "±1%")
        (field (name "VOLTAGE") "75V")
      )
      (libsource (lib "ea_PassivComps") (part "Resistor"))
    )
    (comp (ref "R67")
      (value "0.004 R")
      (footprint "CSNL2512 CURR SENS")
      (description "Curr.sens.res. 0.004 OHM, 2W, 1% , ±50ppm/°C, 2512 (6432 Metric)")
      (fields (field (name "MANUFACTURER") "Stackpole Electronics Inc.") (field (name "TOLERANCE") "±1%"))
      (libsource (lib "") (part "CSNL2512FT4L00_1"))
    )
    (comp (ref "R68")
      (value "5,1 k")
      (footprint "0603")
      (fields
        (field (name "MANUFACTURER") "Vishay Dale")
        (field (name "TOLERANCE") "±0.1%")
        (field (name "VOLTAGE") "75V")
      )
      (libsource (lib "ea_PassivComps") (part "Resistor"))
    )
    (comp (ref "R69")
      (value "5,1 k")
      (footprint "0603")
      (fields
        (field (name "MANUFACTURER") "Vishay Dale")
        (field (name "TOLERANCE") "±0.1%")
        (field (name "VOLTAGE") "75V")
      )
      (libsource (lib "ea_PassivComps") (part "Resistor"))
    )
    (comp (ref "R70")
      (value "100")
      (footprint "0603")
      (fields
        (field (name "MANUFACTURER") "Stackpole Electronics Inc.")
        (field (name "TOLERANCE") "±1%")
        (field (name "VOLTAGE") "75V")
      )
      (libsource (lib "") (part "Resistor_3"))
    )
    (comp (ref "R71")
      (value "100 k")
      (footprint "0603")
      (fields
        (field (name "MANUFACTURER") "Susumu")
        (field (name "TOLERANCE") "±0.1%")
        (field (name "VOLTAGE") "75V")
      )
      (libsource (lib "ea_PassivComps") (part "Resistor"))
    )
    (comp (ref "R72")
      (value "100")
      (footprint "0603")
      (fields
        (field (name "MANUFACTURER") "Stackpole Electronics Inc.")
        (field (name "TOLERANCE") "±1%")
        (field (name "VOLTAGE") "75V")
      )
      (libsource (lib "") (part "Resistor_2"))
    )
    (comp (ref "R73")
      (value "100 k")
      (footprint "0603")
      (fields
        (field (name "MANUFACTURER") "Susumu")
        (field (name "TOLERANCE") "±0.1%")
        (field (name "VOLTAGE") "75V")
      )
      (libsource (lib "ea_PassivComps") (part "Resistor"))
    )
    (comp (ref "U8")
      (value "TMC6200-TA")
      (footprint "TQFP48-EP")
      (fields
        (field (name "MANUFACTURER") "Trinamic Motion Control GmbH")
        (field (name "PARTNUM") "1460-1384-ND")
        (field (name "PARTNAME") "TMC6200-TA")
      )
      (libsource (lib "ea_IC_motor_control") (part "TMC6200-TA"))
    )
    (comp (ref "U9")
      (value "INA186A2IDDFR")
      (footprint "TSOT-23-8 TI")
      (fields
        (field (name "MANUFACTURER") "Texas Instruments")
        (field (name "PARTNUM") "296-INA186A2IDDFRCT-ND")
      )
      (libsource (lib "ea_IC_sensors") (part "INA186A2IDDFR"))
    )
    (comp (ref "U10")
      (value "TSR 1-2450")
      (footprint "TSR 1 Traco Power")
      (description "Linear Regulator Replacement DC DC Converter 5W, 5V, 1A, 6.5V - 36V Input, -40°C ~ 85°C")
      (fields (field (name "MANUFACTURER") "Traco Power") (field (name "PARTNUM") "1951-2747-ND"))
      (libsource (lib "ea_IC_Power_Reg_Ref_Sw") (part "TSR 1-2450"))
    )
    (comp (ref "U11")
      (value "AP7361C-33SP-13")
      (footprint "SOIC-8 EDP")
      (description "LDO, 3.3 V, 1A, 0.36V@1A, Vin=6V max, -40..+85C, 8-SO-EP")
      (fields
        (field (name "PARTNUM") "AP7361C-33SP-13DICT-ND")
        (field (name "MANUFACTURER") "Diodes Incorporated")
      )
      (libsource (lib "ea_IC_Power_Reg_Ref_Sw") (part "AP7361C-33SP-13"))
    )
    (comp (ref "U12")
      (value "LP5907QMFX-3.3Q1")
      (footprint "SOT23-5")
      (description "LDO 3.3 V, 250 mA, Vin < 5.5V, Iq < 12uA, -40..+125 C, SOT23-5")
      (fields (field (name "MANUFACTURER") "Texas Instruments") (field (name "PARTNUM") "296-40365-1-ND"))
      (libsource (lib "ea_IC_Power_Reg_Ref_Sw") (part "LP5907QMFX-3.3Q1"))
    )
    (comp (ref "U13")
      (value "THS4281DBVR")
      (footprint "SOT23-5")
      (description "Voltage Feedback Amplifier 1 Circuit Rail-to-Rail SOT-23-5")
      (fields (field (name "MANUFACTURER") "Texas Instruments") (field (name "PARTNUM") "296-39224-1-ND"))
      (libsource (lib "ea_IC_OPAmps_AnComparators") (part "THS4281DBVR"))
    )
    (comp (ref "VD5")
      (value "MBR260HW")
      (footprint "SOD-123")
      (description "Diode Schottky  60V, 2A, 660mV @ 2A, -, SOD-123, -55°C ~ 150°C")
      (fields
        (field (name "PARTNAME") "MBR260HW")
        (field (name "PART NUMBER") "APD240KDTR-G1")
        (field (name "MANUFACTURER") "Diodes Incorporated")
      )
      (libsource (lib "ea_ActiveComps") (part "Schottky"))
    )
    (comp (ref "VD6")
      (value "SMAJ30A-13-F")
      (footprint "SMA")
      (description "48.4V Clamp 8.3A Ipp Tvs Diode Surface Mount SMA,")
      (fields (field (name "MANUFACTURER") "Diodes Incorporated") (field (name "PARTNUM") "SMAJ30A-FDICT-ND"))
      (libsource (lib "ea_TVS_protection") (part "SMAJ30A-13-F"))
    )
    (comp (ref "VD7")
      (value "SMAJ5.0A")
      (footprint "SMA")
      (description "9.2V Clamp 43.5A Ipp Tvs Diode Surface Mount SMA, -55°C ~ 150°C (TJ)")
      (fields (field (name "MANUFACTURER") "Littelfuse Inc.") (field (name "PARTNUM") "SMAJ5.0ALFCT-ND"))
      (libsource (lib "ea_TVS_protection") (part "SMAJ5.0A"))
    )
    (comp (ref "X8")
      (value "B8B-XH-A(LF)(SN)")
      (footprint "B8B-XH-A")
      (description "CONN HEADER XH TOP 8POS 2.5MM")
      (fields (field (name "MANUFACTURER") "JST Sales America Inc.") (field (name "PARTNUM") "455-2251-ND"))
      (libsource (lib "ea_Connectors_2.5_mm_pitch") (part "B8B-XH-A(LF)(SN)"))
    )
  )
  (nets
    (net (code "1") (name "+3.3ADCV") (class "Default")
      (node (ref "C57") (pin "2") (pinfunction "2_2") (pintype "passive"))
      (node (ref "C58") (pin "1") (pinfunction "1_1") (pintype "passive"))
      (node (ref "C59") (pin "2") (pinfunction "2_2") (pintype "passive"))
      (node (ref "R29") (pin "2") (pinfunction "2_2") (pintype "passive"))
      (node (ref "R71") (pin "2") (pinfunction "2_2") (pintype "passive"))
      (node (ref "U12") (pin "5") (pinfunction "OUT_5") (pintype "power_in"))
      (node (ref "U13") (pin "5") (pinfunction "V+_5") (pintype "power_in"))
      (node (ref "U9") (pin "1") (pinfunction "VS_1") (pintype "passive"))
      (node (ref "U9") (pin "2") (pinfunction "EN_2") (pintype "passive"))
    )
    (net (code "2") (name "+3V3") (class "Default")
      (node (ref "C32") (pin "2") (pinfunction "2_2") (pintype "passive"))
      (node (ref "C62") (pin "1") (pinfunction "1_1") (pintype "passive"))
      (node (ref "C63") (pin "1") (pinfunction "1_1") (pintype "passive"))
      (node (ref "R52") (pin "1") (pinfunction "1_1") (pintype "passive"))
      (node (ref "U11") (pin "1") (pinfunction "OUT_1") (pintype "passive"))
      (node (ref "U8") (pin "19") (pinfunction "VCC_IO_19") (pintype "power_in"))
    )
    (net (code "3") (name "+5V") (class "Default")
      (node (ref "C60") (pin "1") (pinfunction "1_1") (pintype "passive"))
      (node (ref "C61") (pin "1") (pinfunction "1_1") (pintype "passive"))
      (node (ref "C64") (pin "1") (pinfunction "1_1") (pintype "passive"))
      (node (ref "R60") (pin "1") (pinfunction "1_1") (pintype "passive"))
      (node (ref "R61") (pin "1") (pinfunction "1_1") (pintype "passive"))
      (node (ref "R62") (pin "1") (pinfunction "1_1") (pintype "passive"))
      (node (ref "R64") (pin "2") (pinfunction "2_2") (pintype "passive"))
      (node (ref "U10") (pin "3") (pinfunction "OUT_3") (pintype "power_in"))
      (node (ref "U11") (pin "2") (pinfunction "EN_2") (pintype "passive"))
      (node (ref "U11") (pin "8") (pinfunction "VIN_8") (pintype "passive"))
      (node (ref "U12") (pin "1") (pinfunction "IN_1") (pintype "power_in"))
      (node (ref "U12") (pin "3") (pinfunction "EN_3") (pintype "power_in"))
      (node (ref "VD7") (pin "1") (pinfunction "1_1") (pintype "passive"))
      (node (ref "X8") (pin "8") (pinfunction "+5V_RED_8") (pintype "passive"))
    )
    (net (code "4") (name "+PVDD") (class "Default")
      (node (ref "B8") (pin "2") (pinfunction "2_2") (pintype "passive"))
      (node (ref "C30") (pin "2") (pinfunction "2_2") (pintype "passive"))
      (node (ref "C31") (pin "2") (pinfunction "2_2") (pintype "passive"))
      (node (ref "C35") (pin "1") (pinfunction "1_1") (pintype "passive"))
      (node (ref "C36") (pin "1") (pinfunction "1_1") (pintype "passive"))
      (node (ref "C37") (pin "1") (pinfunction "1_1") (pintype "passive"))
      (node (ref "C38") (pin "1") (pinfunction "1_1") (pintype "passive"))
      (node (ref "C39") (pin "1") (pinfunction "1_1") (pintype "passive"))
      (node (ref "C40") (pin "1") (pinfunction "1_1") (pintype "passive"))
      (node (ref "C41") (pin "2") (pinfunction "2_2") (pintype "passive"))
      (node (ref "C88") (pin "1") (pinfunction "1_1") (pintype "passive"))
      (node (ref "C89") (pin "1") (pinfunction "1_1") (pintype "passive"))
      (node (ref "Q1") (pin "3") (pinfunction "D_3") (pintype "passive"))
      (node (ref "Q2") (pin "3") (pinfunction "D_3") (pintype "passive"))
      (node (ref "Q3") (pin "3") (pinfunction "D_3") (pintype "passive"))
      (node (ref "R63") (pin "2") (pinfunction "2_2") (pintype "passive"))
      (node (ref "R67") (pin "1") (pinfunction "1_1") (pintype "passive"))
      (node (ref "U8") (pin "29") (pinfunction "VSA_29") (pintype "power_in"))
      (node (ref "U8") (pin "33") (pinfunction "VS_33") (pintype "power_in"))
      (node (ref "VD5") (pin "2") (pinfunction "A_2") (pintype "passive"))
    )
    (net (code "5") (name "/ENCU") (class "Default")
      (node (ref "R53") (pin "1") (pinfunction "1_1") (pintype "passive"))
      (node (ref "R62") (pin "2") (pinfunction "2_2") (pintype "passive"))
      (node (ref "X8") (pin "5") (pinfunction "HU_BLUE_5") (pintype "passive"))
    )
    (net (code "6") (name "/ENCV") (class "Default")
      (node (ref "R54") (pin "1") (pinfunction "1_1") (pintype "passive"))
      (node (ref "R61") (pin "2") (pinfunction "2_2") (pintype "passive"))
      (node (ref "X8") (pin "6") (pinfunction "HW_WHITE_6") (pintype "passive"))
    )
    (net (code "7") (name "/ENCW") (class "Default")
      (node (ref "R55") (pin "1") (pinfunction "1_1") (pintype "passive"))
      (node (ref "R60") (pin "2") (pinfunction "2_2") (pintype "passive"))
      (node (ref "X8") (pin "7") (pinfunction "HV_GREEN_7") (pintype "passive"))
    )
    (net (code "8") (name "/ENC_U") (class "Default")
      (node (ref "C50") (pin "1") (pinfunction "1_1") (pintype "passive"))
      (node (ref "R53") (pin "2") (pinfunction "2_2") (pintype "passive"))
      (node (ref "R57") (pin "2") (pinfunction "2_2") (pintype "passive"))
    )
    (net (code "9") (name "/ENC_V") (class "Default")
      (node (ref "C51") (pin "1") (pinfunction "1_1") (pintype "passive"))
      (node (ref "R54") (pin "2") (pinfunction "2_2") (pintype "passive"))
      (node (ref "R58") (pin "2") (pinfunction "2_2") (pintype "passive"))
    )
    (net (code "10") (name "/ENC_W") (class "Default")
      (node (ref "C52") (pin "1") (pinfunction "1_1") (pintype "passive"))
      (node (ref "R55") (pin "2") (pinfunction "2_2") (pintype "passive"))
      (node (ref "R59") (pin "2") (pinfunction "2_2") (pintype "passive"))
    )
    (net (code "11") (name "/GPT0_A") (class "Default")
      (node (ref "R30") (pin "1") (pinfunction "1_1") (pintype "passive"))
    )
    (net (code "12") (name "/GPT0_B") (class "Default")
      (node (ref "R36") (pin "1") (pinfunction "1_1") (pintype "passive"))
    )
    (net (code "13") (name "/GPT1_A") (class "Default")
      (node (ref "R42") (pin "1") (pinfunction "1_1") (pintype "passive"))
    )
    (net (code "14") (name "/GPT1_B") (class "Default")
      (node (ref "R45") (pin "1") (pinfunction "1_1") (pintype "passive"))
    )
    (net (code "15") (name "/GPT2_A") (class "Default")
      (node (ref "R47") (pin "1") (pinfunction "1_1") (pintype "passive"))
    )
    (net (code "16") (name "/GPT2_B") (class "Default")
      (node (ref "R49") (pin "1") (pinfunction "1_1") (pintype "passive"))
    )
    (net (code "17") (name "/HSU") (class "Default")
      (node (ref "Q3") (pin "1") (pinfunction "G_1") (pintype "passive"))
      (node (ref "U8") (pin "48") (pinfunction "HSU_48") (pintype "power_in"))
    )
    (net (code "18") (name "/HSV") (class "Default")
      (node (ref "Q2") (pin "1") (pinfunction "G_1") (pintype "passive"))
      (node (ref "U8") (pin "43") (pinfunction "HSV_43") (pintype "power_in"))
    )
    (net (code "19") (name "/HSW") (class "Default")
      (node (ref "Q1") (pin "1") (pinfunction "G_1") (pintype "passive"))
      (node (ref "U8") (pin "37") (pinfunction "HSW_37") (pintype "power_in"))
    )
    (net (code "20") (name "/LSU") (class "Default")
      (node (ref "Q6") (pin "1") (pinfunction "G_1") (pintype "passive"))
      (node (ref "U8") (pin "5") (pinfunction "LSU_5") (pintype "power_in"))
    )
    (net (code "21") (name "/LSV") (class "Default")
      (node (ref "Q5") (pin "1") (pinfunction "G_1") (pintype "passive"))
      (node (ref "U8") (pin "4") (pinfunction "LSV_4") (pintype "power_in"))
    )
    (net (code "22") (name "/LSW") (class "Default")
      (node (ref "Q4") (pin "1") (pinfunction "G_1") (pintype "passive"))
      (node (ref "U8") (pin "3") (pinfunction "LSW_3") (pintype "power_in"))
    )
    (net (code "23") (name "/MDRV_CLK") (class "Default")
      (node (ref "U8") (pin "14") (pinfunction "SCK_IDRV1_14") (pintype "power_in"))
    )
    (net (code "24") (name "/MDRV_EN") (class "Default")
      (node (ref "U8") (pin "27") (pinfunction "DRV_EN_27") (pintype "power_in"))
    )
    (net (code "25") (name "/MDRV_FAULT") (class "Default")
      (node (ref "U8") (pin "26") (pinfunction "FAULT_26") (pintype "power_in"))
    )
    (net (code "26") (name "/MDRV_MISO") (class "Default")
      (node (ref "U8") (pin "16") (pinfunction "SDO_SINGLE_16") (pintype "power_in"))
    )
    (net (code "27") (name "/MDRV_MOSI") (class "Default")
      (node (ref "U8") (pin "15") (pinfunction "SDI_AMPLx10_15") (pintype "power_in"))
    )
    (net (code "28") (name "/MDRV_SC") (class "Default")
      (node (ref "U8") (pin "13") (pinfunction "CSN_IDRV0_13") (pintype "power_in"))
    )
    (net (code "29") (name "/MOT_U") (class "Default")
      (node (ref "B6") (pin "1") (pinfunction "1_1") (pintype "passive"))
      (node (ref "C47") (pin "1") (pinfunction "1_1") (pintype "passive"))
      (node (ref "P3") (pin "1") (pinfunction "1_1") (pintype "passive"))
      (node (ref "R34") (pin "2") (pinfunction "2_2") (pintype "passive"))
      (node (ref "X8") (pin "3") (pinfunction "U_YELLOW_3") (pintype "passive"))
    )
    (net (code "30") (name "/MOT_V") (class "Default")
      (node (ref "B5") (pin "1") (pinfunction "1_1") (pintype "passive"))
      (node (ref "C46") (pin "1") (pinfunction "1_1") (pintype "passive"))
      (node (ref "P2") (pin "1") (pinfunction "1_1") (pintype "passive"))
      (node (ref "R33") (pin "2") (pinfunction "2_2") (pintype "passive"))
      (node (ref "X8") (pin "2") (pinfunction "W_BLACK_2") (pintype "passive"))
    )
    (net (code "31") (name "/MOT_W") (class "Default")
      (node (ref "B4") (pin "1") (pinfunction "1_1") (pintype "passive"))
      (node (ref "C45") (pin "1") (pinfunction "1_1") (pintype "passive"))
      (node (ref "P1") (pin "1") (pinfunction "1_1") (pintype "passive"))
      (node (ref "R32") (pin "2") (pinfunction "2_2") (pintype "passive"))
      (node (ref "X8") (pin "1") (pinfunction "V_RED_1") (pintype "passive"))
    )
    (net (code "32") (name "/TEMP") (class "Default")
      (node (ref "C44") (pin "2") (pinfunction "2_2") (pintype "passive"))
      (node (ref "R29") (pin "1") (pinfunction "1_1") (pintype "passive"))
      (node (ref "R37") (pin "2") (pinfunction "2_2") (pintype "passive"))
    )
    (net (code "33") (name "/U") (class "Default")
      (node (ref "B3") (pin "2") (pinfunction "2_2") (pintype "passive"))
      (node (ref "C43") (pin "2") (pinfunction "2_2") (pintype "passive"))
      (node (ref "U8") (pin "47") (pinfunction "U_47") (pintype "power_in"))
    )
    (net (code "34") (name "/UH") (class "Default")
      (node (ref "R35") (pin "1") (pinfunction "1_1") (pintype "passive"))
    )
    (net (code "35") (name "/UL") (class "Default")
      (node (ref "R38") (pin "1") (pinfunction "1_1") (pintype "passive"))
    )
    (net (code "36") (name "/USNS") (class "Default")
      (node (ref "B6") (pin "2") (pinfunction "2_2") (pintype "passive"))
      (node (ref "R43") (pin "2") (pinfunction "2_2") (pintype "passive"))
    )
    (net (code "37") (name "/V") (class "Default")
      (node (ref "B2") (pin "2") (pinfunction "2_2") (pintype "passive"))
      (node (ref "C48") (pin "2") (pinfunction "2_2") (pintype "passive"))
      (node (ref "U8") (pin "42") (pinfunction "V_42") (pintype "power_in"))
    )
    (net (code "38") (name "/VH") (class "Default")
      (node (ref "R44") (pin "1") (pinfunction "1_1") (pintype "passive"))
    )
    (net (code "39") (name "/VL") (class "Default")
      (node (ref "R46") (pin "1") (pinfunction "1_1") (pintype "passive"))
    )
    (net (code "40") (name "/VREF_R") (class "Default")
      (node (ref "C67") (pin "1") (pinfunction "1_1") (pintype "passive"))
      (node (ref "R72") (pin "1") (pinfunction "1_1") (pintype "passive"))
      (node (ref "U8") (pin "12") (pinfunction "VOFS/TEST_12") (pintype "power_in"))
    )
    (net (code "41") (name "/VSNS") (class "Default")
      (node (ref "B5") (pin "2") (pinfunction "2_2") (pintype "passive"))
      (node (ref "R50") (pin "2") (pinfunction "2_2") (pintype "passive"))
    )
    (net (code "42") (name "/V_IPWR") (class "Default")
      (node (ref "C53") (pin "2") (pinfunction "2_2") (pintype "passive"))
      (node (ref "R66") (pin "2") (pinfunction "2_2") (pintype "passive"))
    )
    (net (code "43") (name "/V_IU") (class "Default")
      (node (ref "U8") (pin "9") (pinfunction "CURU_9") (pintype "power_in"))
    )
    (net (code "44") (name "/V_IV") (class "Default")
      (node (ref "U8") (pin "10") (pinfunction "CURV_10") (pintype "power_in"))
    )
    (net (code "45") (name "/V_IW") (class "Default")
      (node (ref "U8") (pin "11") (pinfunction "CURW_11") (pintype "power_in"))
    )
    (net (code "46") (name "/V_V5V") (class "Default")
      (node (ref "C56") (pin "1") (pinfunction "1_1") (pintype "passive"))
      (node (ref "R64") (pin "1") (pinfunction "1_1") (pintype "passive"))
      (node (ref "R69") (pin "2") (pinfunction "2_2") (pintype "passive"))
    )
    (net (code "47") (name "/V_VPWR") (class "Default")
      (node (ref "C55") (pin "1") (pinfunction "1_1") (pintype "passive"))
      (node (ref "R63") (pin "1") (pinfunction "1_1") (pintype "passive"))
      (node (ref "R68") (pin "2") (pinfunction "2_2") (pintype "passive"))
    )
    (net (code "48") (name "/W") (class "Default")
      (node (ref "B1") (pin "2") (pinfunction "2_2") (pintype "passive"))
      (node (ref "C49") (pin "2") (pinfunction "2_2") (pintype "passive"))
      (node (ref "U8") (pin "38") (pinfunction "W_38") (pintype "power_in"))
    )
    (net (code "49") (name "/WH") (class "Default")
      (node (ref "R48") (pin "1") (pinfunction "1_1") (pintype "passive"))
    )
    (net (code "50") (name "/WL") (class "Default")
      (node (ref "R51") (pin "1") (pinfunction "1_1") (pintype "passive"))
    )
    (net (code "51") (name "/WSNS") (class "Default")
      (node (ref "B4") (pin "2") (pinfunction "2_2") (pintype "passive"))
      (node (ref "R56") (pin "2") (pinfunction "2_2") (pintype "passive"))
    )
    (net (code "52") (name "GND") (class "Default")
      (node (ref "C30") (pin "1") (pinfunction "1_1") (pintype "passive"))
      (node (ref "C31") (pin "1") (pinfunction "1_1") (pintype "passive"))
      (node (ref "C32") (pin "1") (pinfunction "1_1") (pintype "passive"))
      (node (ref "C33") (pin "1") (pinfunction "1_1") (pintype "passive"))
      (node (ref "C34") (pin "1") (pinfunction "1_1") (pintype "passive"))
      (node (ref "C35") (pin "2") (pinfunction "2_2") (pintype "passive"))
      (node (ref "C36") (pin "2") (pinfunction "2_2") (pintype "passive"))
      (node (ref "C37") (pin "2") (pinfunction "2_2") (pintype "passive"))
      (node (ref "C38") (pin "2") (pinfunction "2_2") (pintype "passive"))
      (node (ref "C39") (pin "2") (pinfunction "2_2") (pintype "passive"))
      (node (ref "C40") (pin "2") (pinfunction "2_2") (pintype "passive"))
      (node (ref "C44") (pin "1") (pinfunction "1_1") (pintype "passive"))
      (node (ref "C50") (pin "2") (pinfunction "2_2") (pintype "passive"))
      (node (ref "C51") (pin "2") (pinfunction "2_2") (pintype "passive"))
      (node (ref "C52") (pin "2") (pinfunction "2_2") (pintype "passive"))
      (node (ref "C53") (pin "1") (pinfunction "1_1") (pintype "passive"))
      (node (ref "C55") (pin "2") (pinfunction "2_2") (pintype "passive"))
      (node (ref "C56") (pin "2") (pinfunction "2_2") (pintype "passive"))
      (node (ref "C57") (pin "1") (pinfunction "1_1") (pintype "passive"))
      (node (ref "C58") (pin "2") (pinfunction "2_2") (pintype "passive"))
      (node (ref "C59") (pin "1") (pinfunction "1_1") (pintype "passive"))
      (node (ref "C60") (pin "2") (pinfunction "2_2") (pintype "passive"))
      (node (ref "C61") (pin "2") (pinfunction "2_2") (pintype "passive"))
      (node (ref "C62") (pin "2") (pinfunction "2_2") (pintype "passive"))
      (node (ref "C63") (pin "2") (pinfunction "2_2") (pintype "passive"))
      (node (ref "C64") (pin "2") (pinfunction "2_2") (pintype "passive"))
      (node (ref "C65") (pin "1") (pinfunction "1_1") (pintype "passive"))
      (node (ref "C66") (pin "1") (pinfunction "1_1") (pintype "passive"))
      (node (ref "C67") (pin "2") (pinfunction "2_2") (pintype "passive"))
      (node (ref "C88") (pin "2") (pinfunction "2_2") (pintype "passive"))
      (node (ref "C89") (pin "2") (pinfunction "2_2") (pintype "passive"))
      (node (ref "P5") (pin "1") (pinfunction "1_1") (pintype "passive"))
      (node (ref "Q4") (pin "2") (pinfunction "S_2") (pintype "passive"))
      (node (ref "Q5") (pin "2") (pinfunction "S_2") (pintype "passive"))
      (node (ref "Q6") (pin "2") (pinfunction "S_2") (pintype "passive"))
      (node (ref "R31") (pin "1") (pinfunction "1_1") (pintype "passive"))
      (node (ref "R37") (pin "1") (pinfunction "1_1") (pintype "passive"))
      (node (ref "R39") (pin "1") (pinfunction "1_1") (pintype "passive"))
      (node (ref "R40") (pin "1") (pinfunction "1_1") (pintype "passive"))
      (node (ref "R41") (pin "1") (pinfunction "1_1") (pintype "passive"))
      (node (ref "R57") (pin "1") (pinfunction "1_1") (pintype "passive"))
      (node (ref "R58") (pin "1") (pinfunction "1_1") (pintype "passive"))
      (node (ref "R59") (pin "1") (pinfunction "1_1") (pintype "passive"))
      (node (ref "R68") (pin "1") (pinfunction "1_1") (pintype "passive"))
      (node (ref "R69") (pin "1") (pinfunction "1_1") (pintype "passive"))
      (node (ref "R73") (pin "1") (pinfunction "1_1") (pintype "passive"))
      (node (ref "U10") (pin "2") (pinfunction "GND_2") (pintype "power_in"))
      (node (ref "U11") (pin "4") (pinfunction "GND_4") (pintype "passive"))
      (node (ref "U11") (pin "9") (pinfunction "EP_9") (pintype "passive"))
      (node (ref "U12") (pin "2") (pinfunction "GND_2") (pintype "power_in"))
      (node (ref "U13") (pin "2") (pinfunction "GND_2") (pintype "power_in"))
      (node (ref "U8") (pin "0") (pinfunction "GND_0") (pintype "power_in"))
      (node (ref "U8") (pin "8") (pinfunction "GNDA_8") (pintype "power_in"))
      (node (ref "U9") (pin "3") (pinfunction "REF_3") (pintype "passive"))
      (node (ref "U9") (pin "4") (pinfunction "GND_4") (pintype "passive"))
      (node (ref "VD6") (pin "2") (pinfunction "2_2") (pintype "passive"))
      (node (ref "VD7") (pin "2") (pinfunction "2_2") (pintype "passive"))
      (node (ref "X8") (pin "4") (pinfunction "GND_BLACK_4") (pintype "passive"))
    )
    (net (code "53") (name "Net-(B7-Pad1)") (class "Default")
      (node (ref "B7") (pin "1") (pinfunction "1_1") (pintype "passive"))
      (node (ref "R65") (pin "1") (pinfunction "1_1") (pintype "passive"))
    )
    (net (code "54") (name "Net-(B7-Pad2)") (class "Default")
      (node (ref "B7") (pin "2") (pinfunction "2_2") (pintype "passive"))
      (node (ref "P4") (pin "1") (pinfunction "1_1") (pintype "passive"))
      (node (ref "R67") (pin "2") (pinfunction "2_2") (pintype "passive"))
    )
    (net (code "55") (name "Net-(B8-Pad1)") (class "Default")
      (node (ref "B8") (pin "1") (pinfunction "1_1") (pintype "passive"))
      (node (ref "R70") (pin "2") (pinfunction "2_2") (pintype "passive"))
    )
    (net (code "56") (name "Net-(C45-Pad2)") (class "Default")
      (node (ref "C45") (pin "2") (pinfunction "2_2") (pintype "passive"))
      (node (ref "R39") (pin "2") (pinfunction "2_2") (pintype "passive"))
    )
    (net (code "57") (name "Net-(C46-Pad2)") (class "Default")
      (node (ref "C46") (pin "2") (pinfunction "2_2") (pintype "passive"))
      (node (ref "R40") (pin "2") (pinfunction "2_2") (pintype "passive"))
    )
    (net (code "58") (name "Net-(C47-Pad2)") (class "Default")
      (node (ref "C47") (pin "2") (pinfunction "2_2") (pintype "passive"))
      (node (ref "R41") (pin "2") (pinfunction "2_2") (pintype "passive"))
    )
    (net (code "59") (name "Net-(Q1-S)") (class "Default")
      (node (ref "B1") (pin "1") (pinfunction "1_1") (pintype "passive"))
      (node (ref "Q1") (pin "2") (pinfunction "S_2") (pintype "passive"))
      (node (ref "Q4") (pin "3") (pinfunction "D_3") (pintype "passive"))
      (node (ref "R32") (pin "1") (pinfunction "1_1") (pintype "passive"))
    )
    (net (code "60") (name "Net-(Q2-S)") (class "Default")
      (node (ref "B2") (pin "1") (pinfunction "1_1") (pintype "passive"))
      (node (ref "Q2") (pin "2") (pinfunction "S_2") (pintype "passive"))
      (node (ref "Q5") (pin "3") (pinfunction "D_3") (pintype "passive"))
      (node (ref "R33") (pin "1") (pinfunction "1_1") (pintype "passive"))
    )
    (net (code "61") (name "Net-(Q3-S)") (class "Default")
      (node (ref "B3") (pin "1") (pinfunction "1_1") (pintype "passive"))
      (node (ref "Q3") (pin "2") (pinfunction "S_2") (pintype "passive"))
      (node (ref "Q6") (pin "3") (pinfunction "D_3") (pintype "passive"))
      (node (ref "R34") (pin "1") (pinfunction "1_1") (pintype "passive"))
    )
    (net (code "62") (name "Net-(U8-5VOUT)") (class "Default")
      (node (ref "C33") (pin "2") (pinfunction "2_2") (pintype "passive"))
      (node (ref "U8") (pin "7") (pinfunction "5VOUT_7") (pintype "power_in"))
    )
    (net (code "63") (name "Net-(U8-12VOUT)") (class "Default")
      (node (ref "C34") (pin "2") (pinfunction "2_2") (pintype "passive"))
      (node (ref "U8") (pin "6") (pinfunction "12VOUT_6") (pintype "power_in"))
    )
    (net (code "64") (name "Net-(U8-CLK)") (class "Default")
      (node (ref "R31") (pin "2") (pinfunction "2_2") (pintype "passive"))
      (node (ref "U8") (pin "24") (pinfunction "CLK_24") (pintype "power_in"))
    )
    (net (code "65") (name "Net-(U8-CPI)") (class "Default")
      (node (ref "C42") (pin "2") (pinfunction "2_2") (pintype "passive"))
      (node (ref "U8") (pin "32") (pinfunction "CPI_32") (pintype "power_in"))
    )
    (net (code "66") (name "Net-(U8-CPO)") (class "Default")
      (node (ref "C42") (pin "1") (pinfunction "1_1") (pintype "passive"))
      (node (ref "U8") (pin "30") (pinfunction "CPO_30") (pintype "power_in"))
    )
    (net (code "67") (name "Net-(U8-CU)") (class "Default")
      (node (ref "C43") (pin "1") (pinfunction "1_1") (pintype "passive"))
      (node (ref "U8") (pin "1") (pinfunction "CU_1") (pintype "power_in"))
    )
    (net (code "68") (name "Net-(U8-CV)") (class "Default")
      (node (ref "C48") (pin "1") (pinfunction "1_1") (pintype "passive"))
      (node (ref "U8") (pin "44") (pinfunction "CV_44") (pintype "power_in"))
    )
    (net (code "69") (name "Net-(U8-CW)") (class "Default")
      (node (ref "C49") (pin "1") (pinfunction "1_1") (pintype "passive"))
      (node (ref "U8") (pin "36") (pinfunction "CW_36") (pintype "power_in"))
    )
    (net (code "70") (name "Net-(U8-SPE)") (class "Default")
      (node (ref "R52") (pin "2") (pinfunction "2_2") (pintype "passive"))
      (node (ref "U8") (pin "25") (pinfunction "SPE_25") (pintype "power_in"))
    )
    (net (code "71") (name "Net-(U8-UH)") (class "Default")
      (node (ref "R30") (pin "2") (pinfunction "2_2") (pintype "passive"))
      (node (ref "R35") (pin "2") (pinfunction "2_2") (pintype "passive"))
      (node (ref "U8") (pin "17") (pinfunction "UH_17") (pintype "power_in"))
    )
    (net (code "72") (name "Net-(U8-UL)") (class "Default")
      (node (ref "R36") (pin "2") (pinfunction "2_2") (pintype "passive"))
      (node (ref "R38") (pin "2") (pinfunction "2_2") (pintype "passive"))
      (node (ref "U8") (pin "18") (pinfunction "UL_18") (pintype "power_in"))
    )
    (net (code "73") (name "Net-(U8-USENSE)") (class "Default")
      (node (ref "R43") (pin "1") (pinfunction "1_1") (pintype "passive"))
      (node (ref "U8") (pin "46") (pinfunction "USENSE_46") (pintype "power_in"))
    )
    (net (code "74") (name "Net-(U8-VCP)") (class "Default")
      (node (ref "C41") (pin "1") (pinfunction "1_1") (pintype "passive"))
      (node (ref "U8") (pin "34") (pinfunction "VCP_34") (pintype "power_in"))
    )
    (net (code "75") (name "Net-(U8-VH)") (class "Default")
      (node (ref "R42") (pin "2") (pinfunction "2_2") (pintype "passive"))
      (node (ref "R44") (pin "2") (pinfunction "2_2") (pintype "passive"))
      (node (ref "U8") (pin "20") (pinfunction "VH_20") (pintype "power_in"))
    )
    (net (code "76") (name "Net-(U8-VL)") (class "Default")
      (node (ref "R45") (pin "2") (pinfunction "2_2") (pintype "passive"))
      (node (ref "R46") (pin "2") (pinfunction "2_2") (pintype "passive"))
      (node (ref "U8") (pin "21") (pinfunction "VL_21") (pintype "power_in"))
    )
    (net (code "77") (name "Net-(U8-VSENSE)") (class "Default")
      (node (ref "R50") (pin "1") (pinfunction "1_1") (pintype "passive"))
      (node (ref "U8") (pin "41") (pinfunction "VSENSE_41") (pintype "power_in"))
    )
    (net (code "78") (name "Net-(U8-WH)") (class "Default")
      (node (ref "R47") (pin "2") (pinfunction "2_2") (pintype "passive"))
      (node (ref "R48") (pin "2") (pinfunction "2_2") (pintype "passive"))
      (node (ref "U8") (pin "22") (pinfunction "WH_22") (pintype "power_in"))
    )
    (net (code "79") (name "Net-(U8-WL)") (class "Default")
      (node (ref "R49") (pin "2") (pinfunction "2_2") (pintype "passive"))
      (node (ref "R51") (pin "2") (pinfunction "2_2") (pintype "passive"))
      (node (ref "U8") (pin "23") (pinfunction "WL_23") (pintype "power_in"))
    )
    (net (code "80") (name "Net-(U8-WSENSE)") (class "Default")
      (node (ref "R56") (pin "1") (pinfunction "1_1") (pintype "passive"))
      (node (ref "U8") (pin "39") (pinfunction "WSENSE_39") (pintype "power_in"))
    )
    (net (code "81") (name "Net-(U9-IN+)") (class "Default")
      (node (ref "C54") (pin "2") (pinfunction "2_2") (pintype "passive"))
      (node (ref "R65") (pin "2") (pinfunction "2_2") (pintype "passive"))
      (node (ref "U9") (pin "7") (pinfunction "IN+_7") (pintype "passive"))
    )
    (net (code "82") (name "Net-(U9-IN-)") (class "Default")
      (node (ref "C54") (pin "1") (pinfunction "1_1") (pintype "passive"))
      (node (ref "R70") (pin "1") (pinfunction "1_1") (pintype "passive"))
      (node (ref "U9") (pin "8") (pinfunction "IN-_8") (pintype "passive"))
    )
    (net (code "83") (name "Net-(U9-OUT)") (class "Default")
      (node (ref "R66") (pin "1") (pinfunction "1_1") (pintype "passive"))
      (node (ref "U9") (pin "5") (pinfunction "OUT_5") (pintype "passive"))
    )
    (net (code "84") (name "Net-(U10-IN)") (class "Default")
      (node (ref "C65") (pin "2") (pinfunction "2_2") (pintype "passive"))
      (node (ref "U10") (pin "1") (pinfunction "IN_1") (pintype "power_in"))
      (node (ref "VD5") (pin "1") (pinfunction "C_1") (pintype "passive"))
      (node (ref "VD6") (pin "1") (pinfunction "1_1") (pintype "passive"))
    )
    (net (code "85") (name "Net-(U13-IN+)") (class "Default")
      (node (ref "C66") (pin "2") (pinfunction "2_2") (pintype "passive"))
      (node (ref "R71") (pin "1") (pinfunction "1_1") (pintype "passive"))
      (node (ref "R73") (pin "2") (pinfunction "2_2") (pintype "passive"))
      (node (ref "U13") (pin "3") (pinfunction "IN+_3") (pintype "passive"))
    )
    (net (code "86") (name "Net-(U13-IN-)") (class "Default")
      (node (ref "R72") (pin "2") (pinfunction "2_2") (pintype "passive"))
      (node (ref "U13") (pin "1") (pinfunction "OUT_1") (pintype "passive"))
      (node (ref "U13") (pin "4") (pinfunction "IN-_4") (pintype "passive"))
    )
    (net (code "87") (name "unconnected-(U8-NC-Pad2)") (class "Default")
      (node (ref "U8") (pin "2") (pinfunction "NC_2") (pintype "power_in"))
    )
    (net (code "88") (name "unconnected-(U8-NC-Pad28)") (class "Default")
      (node (ref "U8") (pin "28") (pinfunction "NC_28") (pintype "power_in"))
    )
    (net (code "89") (name "unconnected-(U8-NC-Pad31)") (class "Default")
      (node (ref "U8") (pin "31") (pinfunction "NC_31") (pintype "power_in"))
    )
    (net (code "90") (name "unconnected-(U8-NC-Pad35)") (class "Default")
      (node (ref "U8") (pin "35") (pinfunction "NC_35") (pintype "power_in"))
    )
    (net (code "91") (name "unconnected-(U8-NC-Pad40)") (class "Default")
      (node (ref "U8") (pin "40") (pinfunction "NC_40") (pintype "power_in"))
    )
    (net (code "92") (name "unconnected-(U8-NC-Pad45)") (class "Default")
      (node (ref "U8") (pin "45") (pinfunction "NC_45") (pintype "power_in"))
    )
  )
)
